# trans1.net
KiCad netlist of a schematic drawn in EAGLE
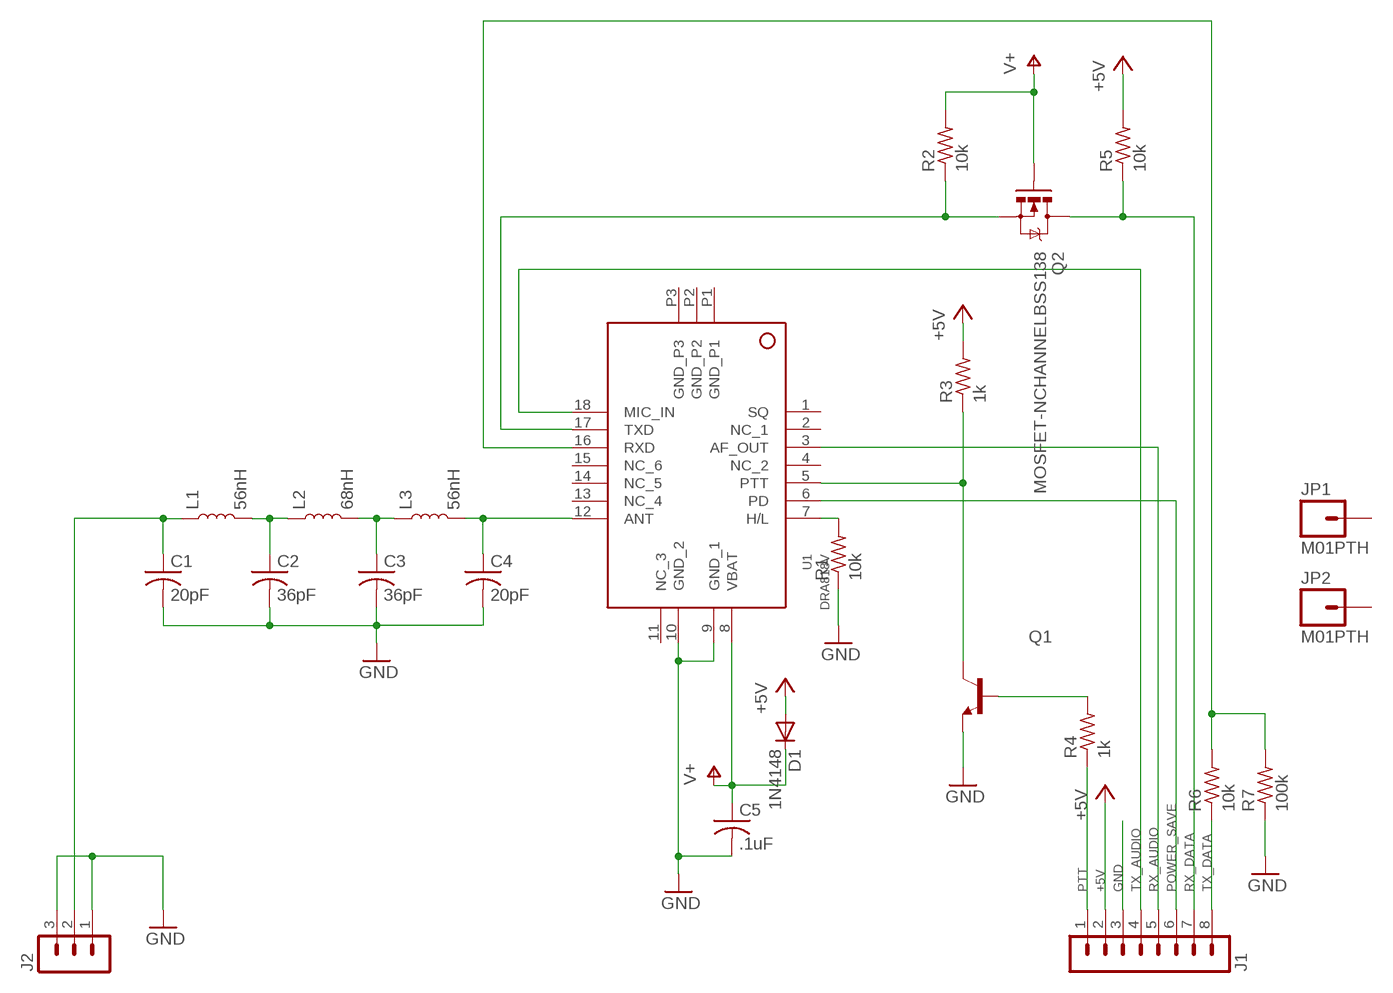
[diagram p0: schematic, sheet 1]

(export (version "E")
  (design (tool "Eeschema 10.0.6"))
  (components
    (comp (ref "C1")
      (value "20pF")
      (footprint "eagle-import:C0805")
      (libsource (lib "eagle-import") (part "C-USC0805"))
    )
    (comp (ref "C2")
      (value "36pF")
      (footprint "eagle-import:C0805")
      (libsource (lib "eagle-import") (part "C-USC0805"))
    )
    (comp (ref "C3")
      (value "36pF")
      (footprint "eagle-import:C0805")
      (libsource (lib "eagle-import") (part "C-USC0805"))
    )
    (comp (ref "C4")
      (value "20pF")
      (footprint "eagle-import:C0805")
      (libsource (lib "eagle-import") (part "C-USC0805"))
    )
    (comp (ref "C5")
      (value ".1uF")
      (footprint "eagle-import:C0805")
      (libsource (lib "eagle-import") (part "C-USC0805"))
    )
    (comp (ref "D1")
      (value "1N4148")
      (footprint "eagle-import:SOD123")
      (libsource (lib "eagle-import") (part "DIODE-SOD123"))
    )
    (comp (ref "J1")
      (value "MA08-1")
      (footprint "eagle-import:MA08-1")
      (libsource (lib "eagle-import") (part "MA08-1"))
    )
    (comp (ref "J2")
      (value "MA03-1")
      (footprint "eagle-import:MA03-1")
      (libsource (lib "eagle-import") (part "MA03-1"))
    )
    (comp (ref "JP1")
      (value "M01PTH")
      (footprint "eagle-import:1X01")
      (libsource (lib "eagle-import") (part "M01PTH"))
    )
    (comp (ref "JP2")
      (value "M01PTH")
      (footprint "eagle-import:1X01")
      (libsource (lib "eagle-import") (part "M01PTH"))
    )
    (comp (ref "L1")
      (value "56nH")
      (footprint "eagle-import:L0805")
      (libsource (lib "eagle-import") (part "INDUCTOR"))
    )
    (comp (ref "L2")
      (value "68nH")
      (footprint "eagle-import:L0805")
      (libsource (lib "eagle-import") (part "INDUCTOR"))
    )
    (comp (ref "L3")
      (value "56nH")
      (footprint "eagle-import:L0805")
      (libsource (lib "eagle-import") (part "INDUCTOR"))
    )
    (comp (ref "Q1")
      (value "BC817-16LT1SMD")
      (footprint "eagle-import:SOT23-BEC")
      (libsource (lib "eagle-import") (part "BC817SMD-16LT1"))
    )
    (comp (ref "Q2")
      (value "MOSFET-NCHANNELBSS138")
      (footprint "eagle-import:SOT23")
      (libsource (lib "eagle-import") (part "MOSFET-NCHANNELBSS138"))
    )
    (comp (ref "R1")
      (value "10k")
      (footprint "eagle-import:R0805")
      (libsource (lib "eagle-import") (part "R-US_R0805"))
    )
    (comp (ref "R2")
      (value "10k")
      (footprint "eagle-import:R0805")
      (libsource (lib "eagle-import") (part "R-US_R0805"))
    )
    (comp (ref "R3")
      (value "1k")
      (footprint "eagle-import:R0805")
      (libsource (lib "eagle-import") (part "R-US_R0805"))
    )
    (comp (ref "R4")
      (value "1k")
      (footprint "eagle-import:R0805")
      (libsource (lib "eagle-import") (part "R-US_R0805"))
    )
    (comp (ref "R5")
      (value "10k")
      (footprint "eagle-import:R0805")
      (libsource (lib "eagle-import") (part "R-US_R0805"))
    )
    (comp (ref "R6")
      (value "10k")
      (footprint "eagle-import:R0805")
      (libsource (lib "eagle-import") (part "R-US_R0805"))
    )
    (comp (ref "R7")
      (value "100k")
      (footprint "eagle-import:R0805")
      (libsource (lib "eagle-import") (part "R-US_R0805"))
    )
    (comp (ref "U1")
      (value "DRA818V")
      (footprint "eagle-import:SMD_DRA818")
      (libsource (lib "eagle-import") (part "DRA818V"))
    )
  )
  (nets
    (net (code "1") (name "+5V") (class "Default")
      (node (ref "D1") (pin "A") (pinfunction "A_A") (pintype "passive"))
      (node (ref "J1") (pin "2") (pinfunction "2_2") (pintype "passive"))
      (node (ref "R3") (pin "2") (pinfunction "2_2") (pintype "passive"))
      (node (ref "R5") (pin "2") (pinfunction "2_2") (pintype "passive"))
    )
    (net (code "2") (name "/POWER_SAVE") (class "Default")
      (node (ref "J1") (pin "6") (pinfunction "6_6") (pintype "passive"))
      (node (ref "U1") (pin "6") (pinfunction "PD_6") (pintype "bidirectional"))
    )
    (net (code "3") (name "/PTT") (class "Default")
      (node (ref "J1") (pin "1") (pinfunction "1_1") (pintype "passive"))
      (node (ref "R4") (pin "1") (pinfunction "1_1") (pintype "passive"))
    )
    (net (code "4") (name "/RX_AUDIO") (class "Default")
      (node (ref "J1") (pin "5") (pinfunction "5_5") (pintype "passive"))
      (node (ref "U1") (pin "3") (pinfunction "AF_OUT_3") (pintype "bidirectional"))
    )
    (net (code "5") (name "/RX_DATA") (class "Default")
      (node (ref "J1") (pin "7") (pinfunction "7_7") (pintype "passive"))
      (node (ref "Q2") (pin "3") (pinfunction "D_3") (pintype "passive"))
      (node (ref "R5") (pin "1") (pinfunction "1_1") (pintype "passive"))
    )
    (net (code "6") (name "/TX_AUDIO") (class "Default")
      (node (ref "J1") (pin "4") (pinfunction "4_4") (pintype "passive"))
      (node (ref "U1") (pin "18") (pinfunction "MIC_IN_18") (pintype "bidirectional"))
    )
    (net (code "7") (name "/TX_DATA") (class "Default")
      (node (ref "J1") (pin "8") (pinfunction "8_8") (pintype "passive"))
      (node (ref "R6") (pin "1") (pinfunction "1_1") (pintype "passive"))
    )
    (net (code "8") (name "GND") (class "Default")
      (node (ref "C1") (pin "2") (pinfunction "2_2") (pintype "passive"))
      (node (ref "C2") (pin "2") (pinfunction "2_2") (pintype "passive"))
      (node (ref "C3") (pin "2") (pinfunction "2_2") (pintype "passive"))
      (node (ref "C4") (pin "2") (pinfunction "2_2") (pintype "passive"))
      (node (ref "C5") (pin "2") (pinfunction "2_2") (pintype "passive"))
      (node (ref "J1") (pin "3") (pinfunction "3_3") (pintype "passive"))
      (node (ref "J2") (pin "1") (pinfunction "1_1") (pintype "passive"))
      (node (ref "J2") (pin "3") (pinfunction "3_3") (pintype "passive"))
      (node (ref "Q1") (pin "E") (pinfunction "E_E") (pintype "passive"))
      (node (ref "R1") (pin "1") (pinfunction "1_1") (pintype "passive"))
      (node (ref "R7") (pin "1") (pinfunction "1_1") (pintype "passive"))
      (node (ref "U1") (pin "10") (pinfunction "GND_2_10") (pintype "bidirectional"))
      (node (ref "U1") (pin "9") (pinfunction "GND_1_9") (pintype "bidirectional"))
    )
    (net (code "9") (name "Net-(C1-Pad1)") (class "Default")
      (node (ref "C1") (pin "1") (pinfunction "1_1") (pintype "passive"))
      (node (ref "J2") (pin "2") (pinfunction "2_2") (pintype "passive"))
      (node (ref "L1") (pin "1") (pinfunction "1_1") (pintype "passive"))
    )
    (net (code "10") (name "Net-(C2-Pad1)") (class "Default")
      (node (ref "C2") (pin "1") (pinfunction "1_1") (pintype "passive"))
      (node (ref "L1") (pin "2") (pinfunction "2_2") (pintype "passive"))
      (node (ref "L2") (pin "1") (pinfunction "1_1") (pintype "passive"))
    )
    (net (code "11") (name "Net-(C3-Pad1)") (class "Default")
      (node (ref "C3") (pin "1") (pinfunction "1_1") (pintype "passive"))
      (node (ref "L2") (pin "2") (pinfunction "2_2") (pintype "passive"))
      (node (ref "L3") (pin "1") (pinfunction "1_1") (pintype "passive"))
    )
    (net (code "12") (name "Net-(Q1-PadB)") (class "Default")
      (node (ref "Q1") (pin "B") (pinfunction "B_B") (pintype "passive"))
      (node (ref "R4") (pin "2") (pinfunction "2_2") (pintype "passive"))
    )
    (net (code "13") (name "Net-(Q2-S)") (class "Default")
      (node (ref "Q2") (pin "2") (pinfunction "S_2") (pintype "passive"))
      (node (ref "R2") (pin "1") (pinfunction "1_1") (pintype "passive"))
      (node (ref "U1") (pin "17") (pinfunction "TXD_17") (pintype "bidirectional"))
    )
    (net (code "14") (name "Net-(U1-ANT)") (class "Default")
      (node (ref "C4") (pin "1") (pinfunction "1_1") (pintype "passive"))
      (node (ref "L3") (pin "2") (pinfunction "2_2") (pintype "passive"))
      (node (ref "U1") (pin "12") (pinfunction "ANT_12") (pintype "bidirectional"))
    )
    (net (code "15") (name "Net-(U1-H{slash}L)") (class "Default")
      (node (ref "R1") (pin "2") (pinfunction "2_2") (pintype "passive"))
      (node (ref "U1") (pin "7") (pinfunction "H/L_7") (pintype "bidirectional"))
    )
    (net (code "16") (name "Net-(U1-PTT)") (class "Default")
      (node (ref "Q1") (pin "C") (pinfunction "C_C") (pintype "passive"))
      (node (ref "R3") (pin "1") (pinfunction "1_1") (pintype "passive"))
      (node (ref "U1") (pin "5") (pinfunction "PTT_5") (pintype "bidirectional"))
    )
    (net (code "17") (name "Net-(U1-RXD)") (class "Default")
      (node (ref "R6") (pin "2") (pinfunction "2_2") (pintype "passive"))
      (node (ref "R7") (pin "2") (pinfunction "2_2") (pintype "passive"))
      (node (ref "U1") (pin "16") (pinfunction "RXD_16") (pintype "bidirectional"))
    )
    (net (code "18") (name "V+") (class "Default")
      (node (ref "C5") (pin "1") (pinfunction "1_1") (pintype "passive"))
      (node (ref "D1") (pin "C") (pinfunction "C_C") (pintype "passive"))
      (node (ref "Q2") (pin "1") (pinfunction "G_1") (pintype "passive"))
      (node (ref "R2") (pin "2") (pinfunction "2_2") (pintype "passive"))
      (node (ref "U1") (pin "8") (pinfunction "VBAT_8") (pintype "bidirectional"))
    )
    (net (code "19") (name "unconnected-(JP1-Pad1)") (class "Default")
      (node (ref "JP1") (pin "1") (pinfunction "1_1") (pintype "passive"))
    )
    (net (code "20") (name "unconnected-(JP2-Pad1)") (class "Default")
      (node (ref "JP2") (pin "1") (pinfunction "1_1") (pintype "passive"))
    )
    (net (code "21") (name "unconnected-(U1-GND_P1-PadP1)") (class "Default")
      (node (ref "U1") (pin "P1") (pinfunction "GND_P1_P1") (pintype "bidirectional"))
    )
    (net (code "22") (name "unconnected-(U1-GND_P2-PadP2)") (class "Default")
      (node (ref "U1") (pin "P2") (pinfunction "GND_P2_P2") (pintype "bidirectional"))
    )
    (net (code "23") (name "unconnected-(U1-GND_P3-PadP3)") (class "Default")
      (node (ref "U1") (pin "P3") (pinfunction "GND_P3_P3") (pintype "bidirectional"))
    )
    (net (code "24") (name "unconnected-(U1-NC_1-Pad2)") (class "Default")
      (node (ref "U1") (pin "2") (pinfunction "NC_1_2") (pintype "bidirectional"))
    )
    (net (code "25") (name "unconnected-(U1-NC_2-Pad4)") (class "Default")
      (node (ref "U1") (pin "4") (pinfunction "NC_2_4") (pintype "bidirectional"))
    )
    (net (code "26") (name "unconnected-(U1-NC_3-Pad11)") (class "Default")
      (node (ref "U1") (pin "11") (pinfunction "NC_3_11") (pintype "bidirectional"))
    )
    (net (code "27") (name "unconnected-(U1-NC_4-Pad13)") (class "Default")
      (node (ref "U1") (pin "13") (pinfunction "NC_4_13") (pintype "bidirectional"))
    )
    (net (code "28") (name "unconnected-(U1-NC_5-Pad14)") (class "Default")
      (node (ref "U1") (pin "14") (pinfunction "NC_5_14") (pintype "bidirectional"))
    )
    (net (code "29") (name "unconnected-(U1-NC_6-Pad15)") (class "Default")
      (node (ref "U1") (pin "15") (pinfunction "NC_6_15") (pintype "bidirectional"))
    )
    (net (code "30") (name "unconnected-(U1-SQ-Pad1)") (class "Default")
      (node (ref "U1") (pin "1") (pinfunction "SQ_1") (pintype "bidirectional"))
    )
  )
)
